# art_limb.net
KiCad netlist of a schematic drawn in EAGLE
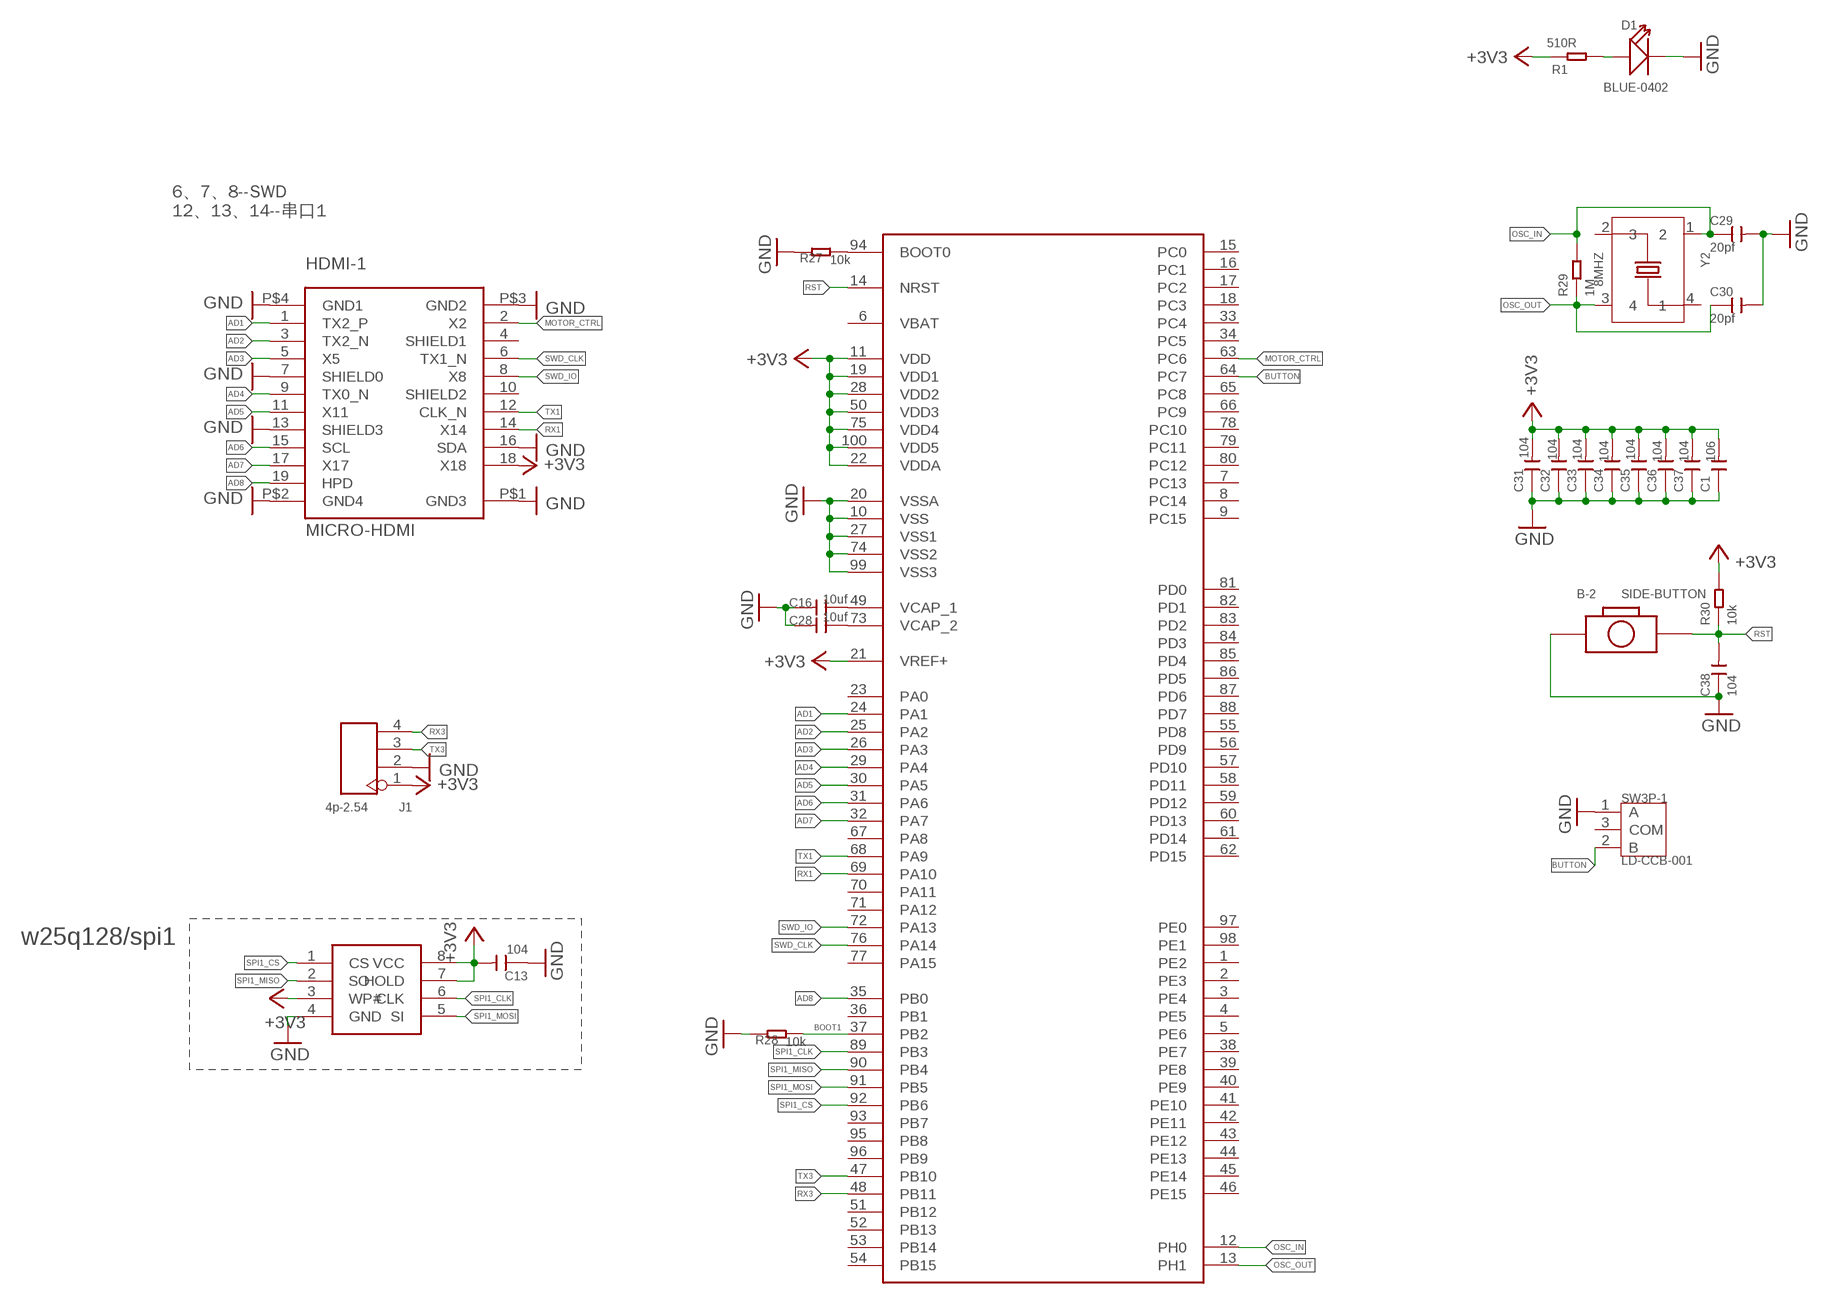
[diagram p0: schematic, sheet 1]

(export (version "E")
  (design (tool "Eeschema 10.0.6"))
  (components
    (comp (ref "B-2")
      (value "SIDE-BUTTON")
      (footprint "eagle-import:SIDE-BUTTON")
      (libsource (lib "eagle-import") (part "SIDE-BUTTON"))
    )
    (comp (ref "C1")
      (value "106")
      (footprint "eagle-import:C0402")
      (fields (field (name "MPN") "GRM1555C1H150JA01D"))
      (libsource (lib "eagle-import") (part "CAP-(0402)"))
    )
    (comp (ref "C13")
      (value "104")
      (footprint "eagle-import:C0402")
      (fields (field (name "MPN") "GRM1555C1H150JA01D"))
      (libsource (lib "eagle-import") (part "CAP-(0402)"))
    )
    (comp (ref "C16")
      (value "10uf")
      (footprint "eagle-import:C0402")
      (fields (field (name "MPN") "GRM1555C1H150JA01D"))
      (libsource (lib "eagle-import") (part "CAP-(0402)"))
    )
    (comp (ref "C28")
      (value "10uf")
      (footprint "eagle-import:C0402")
      (fields (field (name "MPN") "GRM1555C1H150JA01D"))
      (libsource (lib "eagle-import") (part "CAP-(0402)"))
    )
    (comp (ref "C29")
      (value "20pf")
      (footprint "eagle-import:C0402")
      (fields (field (name "MPN") "GRM1555C1H150JA01D"))
      (libsource (lib "eagle-import") (part "CAP-(0402)"))
    )
    (comp (ref "C30")
      (value "20pf")
      (footprint "eagle-import:C0402")
      (fields (field (name "MPN") "GRM1555C1H150JA01D"))
      (libsource (lib "eagle-import") (part "CAP-(0402)"))
    )
    (comp (ref "C31")
      (value "104")
      (footprint "eagle-import:C0402")
      (fields (field (name "MPN") "GRM1555C1H150JA01D"))
      (libsource (lib "eagle-import") (part "CAP-(0402)"))
    )
    (comp (ref "C32")
      (value "104")
      (footprint "eagle-import:C0402")
      (fields (field (name "MPN") "GRM1555C1H150JA01D"))
      (libsource (lib "eagle-import") (part "CAP-(0402)"))
    )
    (comp (ref "C33")
      (value "104")
      (footprint "eagle-import:C0402")
      (fields (field (name "MPN") "GRM1555C1H150JA01D"))
      (libsource (lib "eagle-import") (part "CAP-(0402)"))
    )
    (comp (ref "C34")
      (value "104")
      (footprint "eagle-import:C0402")
      (fields (field (name "MPN") "GRM1555C1H150JA01D"))
      (libsource (lib "eagle-import") (part "CAP-(0402)"))
    )
    (comp (ref "C35")
      (value "104")
      (footprint "eagle-import:C0402")
      (fields (field (name "MPN") "GRM1555C1H150JA01D"))
      (libsource (lib "eagle-import") (part "CAP-(0402)"))
    )
    (comp (ref "C36")
      (value "104")
      (footprint "eagle-import:C0402")
      (fields (field (name "MPN") "GRM1555C1H150JA01D"))
      (libsource (lib "eagle-import") (part "CAP-(0402)"))
    )
    (comp (ref "C37")
      (value "104")
      (footprint "eagle-import:C0402")
      (fields (field (name "MPN") "GRM1555C1H150JA01D"))
      (libsource (lib "eagle-import") (part "CAP-(0402)"))
    )
    (comp (ref "C38")
      (value "104")
      (footprint "eagle-import:C0402")
      (fields (field (name "MPN") "GRM1555C1H150JA01D"))
      (libsource (lib "eagle-import") (part "CAP-(0402)"))
    )
    (comp (ref "D1")
      (value "BLUE-0402")
      (footprint "eagle-import:LED-0402")
      (fields (field (name "MPN") "BL-HB337A-AV-TRB"))
      (libsource (lib "eagle-import") (part "LED-(0402)"))
    )
    (comp (ref "HDMI-1")
      (value "MICRO-HDMI")
      (footprint "eagle-import:HDMI")
      (libsource (lib "eagle-import") (part "MICRO-HDMI"))
    )
    (comp (ref "J1")
      (value "4p-2.54")
      (footprint "eagle-import:H4-2.54")
      (fields (field (name "MPN") "F185-1104A1BSYA1"))
      (libsource (lib "eagle-import") (part "DIP-BLACK-FEMALE-HEADER-VERT(4P-2.54)"))
    )
    (comp (ref "R1")
      (value "510R")
      (footprint "eagle-import:R0402")
      (fields (field (name "MPN") "RC0402JR-070RL"))
      (libsource (lib "eagle-import") (part "RES-(0402)"))
    )
    (comp (ref "R27")
      (value "10k")
      (footprint "eagle-import:R0402")
      (fields (field (name "MPN") "RC0402JR-070RL"))
      (libsource (lib "eagle-import") (part "RES-(0402)"))
    )
    (comp (ref "R28")
      (value "10k")
      (footprint "eagle-import:R0402")
      (fields (field (name "MPN") "RC0402JR-070RL"))
      (libsource (lib "eagle-import") (part "RES-(0402)"))
    )
    (comp (ref "R29")
      (value "1M")
      (footprint "eagle-import:R0402")
      (fields (field (name "MPN") "RC0402JR-070RL"))
      (libsource (lib "eagle-import") (part "RES-(0402)"))
    )
    (comp (ref "R30")
      (value "10k")
      (footprint "eagle-import:R0402")
      (fields (field (name "MPN") "RC0402JR-070RL"))
      (libsource (lib "eagle-import") (part "RES-(0402)"))
    )
    (comp (ref "SW3P-1")
      (value "LD-CCB-001")
      (footprint "eagle-import:SW3-2.54-9.0X3.5X3.5+2.0MM")
      (libsource (lib "eagle-import") (part "SWITCH(3P)"))
    )
    (comp (ref "U$1")
      (value "STM32F40XSTM32D40X")
      (footprint "eagle-import:LQFP100")
      (libsource (lib "eagle-import") (part "STM32F40XSTM32D40X"))
    )
    (comp (ref "W25Q128")
      (value "W25Q128")
      (footprint "eagle-import:SOP08")
      (libsource (lib "eagle-import") (part "W25Q128"))
    )
    (comp (ref "Y2")
      (value "8MHZ")
      (footprint "eagle-import:X4-SMD-3.2X2.5X0.7MM")
      (fields (field (name "MPN") "7M-27.120MAAJ-T"))
      (libsource (lib "eagle-import") (part "SMD-CRYSTAL-27.12MHZ-18PF-30PPM-60R(4P-3.2X2.5MM)"))
    )
  )
  (nets
    (net (code "1") (name "+3V3") (class "Default")
      (node (ref "C1") (pin "2") (pinfunction "2_2") (pintype "passive"))
      (node (ref "C13") (pin "2") (pinfunction "2_2") (pintype "passive"))
      (node (ref "C31") (pin "2") (pinfunction "2_2") (pintype "passive"))
      (node (ref "C32") (pin "2") (pinfunction "2_2") (pintype "passive"))
      (node (ref "C33") (pin "2") (pinfunction "2_2") (pintype "passive"))
      (node (ref "C34") (pin "2") (pinfunction "2_2") (pintype "passive"))
      (node (ref "C35") (pin "2") (pinfunction "2_2") (pintype "passive"))
      (node (ref "C36") (pin "2") (pinfunction "2_2") (pintype "passive"))
      (node (ref "C37") (pin "2") (pinfunction "2_2") (pintype "passive"))
      (node (ref "HDMI-1") (pin "18") (pinfunction "X18_18") (pintype "bidirectional"))
      (node (ref "J1") (pin "1") (pinfunction "P$1_1") (pintype "bidirectional"))
      (node (ref "R1") (pin "2") (pinfunction "2_2") (pintype "passive"))
      (node (ref "R30") (pin "2") (pinfunction "2_2") (pintype "passive"))
      (node (ref "U$1") (pin "100") (pinfunction "VDD5_100") (pintype "bidirectional"))
      (node (ref "U$1") (pin "11") (pinfunction "VDD_11") (pintype "bidirectional"))
      (node (ref "U$1") (pin "19") (pinfunction "VDD1_19") (pintype "bidirectional"))
      (node (ref "U$1") (pin "21") (pinfunction "VREF+_21") (pintype "bidirectional"))
      (node (ref "U$1") (pin "22") (pinfunction "VDDA_22") (pintype "bidirectional"))
      (node (ref "U$1") (pin "28") (pinfunction "VDD2_28") (pintype "bidirectional"))
      (node (ref "U$1") (pin "50") (pinfunction "VDD3_50") (pintype "bidirectional"))
      (node (ref "U$1") (pin "75") (pinfunction "VDD4_75") (pintype "bidirectional"))
      (node (ref "W25Q128") (pin "3") (pinfunction "WP#_3") (pintype "bidirectional"))
      (node (ref "W25Q128") (pin "7") (pinfunction "HOLD_7") (pintype "bidirectional"))
      (node (ref "W25Q128") (pin "8") (pinfunction "VCC_8") (pintype "bidirectional"))
    )
    (net (code "2") (name "/BOOT1") (class "Default")
      (node (ref "R28") (pin "2") (pinfunction "2_2") (pintype "passive"))
      (node (ref "U$1") (pin "37") (pinfunction "PB2_37") (pintype "bidirectional"))
    )
    (net (code "3") (name "AD1") (class "Default")
      (node (ref "HDMI-1") (pin "1") (pinfunction "TX2_P_1") (pintype "bidirectional"))
      (node (ref "U$1") (pin "24") (pinfunction "PA1_24") (pintype "bidirectional"))
    )
    (net (code "4") (name "AD2") (class "Default")
      (node (ref "HDMI-1") (pin "3") (pinfunction "TX2_N_3") (pintype "bidirectional"))
      (node (ref "U$1") (pin "25") (pinfunction "PA2_25") (pintype "bidirectional"))
    )
    (net (code "5") (name "AD3") (class "Default")
      (node (ref "HDMI-1") (pin "5") (pinfunction "X5_5") (pintype "bidirectional"))
      (node (ref "U$1") (pin "26") (pinfunction "PA3_26") (pintype "bidirectional"))
    )
    (net (code "6") (name "AD4") (class "Default")
      (node (ref "HDMI-1") (pin "9") (pinfunction "TX0_N_9") (pintype "bidirectional"))
      (node (ref "U$1") (pin "29") (pinfunction "PA4_29") (pintype "bidirectional"))
    )
    (net (code "7") (name "AD5") (class "Default")
      (node (ref "HDMI-1") (pin "11") (pinfunction "X11_11") (pintype "bidirectional"))
      (node (ref "U$1") (pin "30") (pinfunction "PA5_30") (pintype "bidirectional"))
    )
    (net (code "8") (name "AD6") (class "Default")
      (node (ref "HDMI-1") (pin "15") (pinfunction "SCL_15") (pintype "bidirectional"))
      (node (ref "U$1") (pin "31") (pinfunction "PA6_31") (pintype "bidirectional"))
    )
    (net (code "9") (name "AD7") (class "Default")
      (node (ref "HDMI-1") (pin "17") (pinfunction "X17_17") (pintype "bidirectional"))
      (node (ref "U$1") (pin "32") (pinfunction "PA7_32") (pintype "bidirectional"))
    )
    (net (code "10") (name "AD8") (class "Default")
      (node (ref "HDMI-1") (pin "19") (pinfunction "HPD_19") (pintype "bidirectional"))
      (node (ref "U$1") (pin "35") (pinfunction "PB0_35") (pintype "bidirectional"))
    )
    (net (code "11") (name "BUTTON") (class "Default")
      (node (ref "SW3P-1") (pin "2") (pinfunction "B_2") (pintype "bidirectional"))
      (node (ref "U$1") (pin "64") (pinfunction "PC7_64") (pintype "bidirectional"))
    )
    (net (code "12") (name "GND") (class "Default")
      (node (ref "B-2") (pin "P$2") (pinfunction "1_P$2") (pintype "bidirectional"))
      (node (ref "C1") (pin "1") (pinfunction "1_1") (pintype "passive"))
      (node (ref "C13") (pin "1") (pinfunction "1_1") (pintype "passive"))
      (node (ref "C16") (pin "2") (pinfunction "2_2") (pintype "passive"))
      (node (ref "C28") (pin "2") (pinfunction "2_2") (pintype "passive"))
      (node (ref "C29") (pin "2") (pinfunction "2_2") (pintype "passive"))
      (node (ref "C30") (pin "2") (pinfunction "2_2") (pintype "passive"))
      (node (ref "C31") (pin "1") (pinfunction "1_1") (pintype "passive"))
      (node (ref "C32") (pin "1") (pinfunction "1_1") (pintype "passive"))
      (node (ref "C33") (pin "1") (pinfunction "1_1") (pintype "passive"))
      (node (ref "C34") (pin "1") (pinfunction "1_1") (pintype "passive"))
      (node (ref "C35") (pin "1") (pinfunction "1_1") (pintype "passive"))
      (node (ref "C36") (pin "1") (pinfunction "1_1") (pintype "passive"))
      (node (ref "C37") (pin "1") (pinfunction "1_1") (pintype "passive"))
      (node (ref "C38") (pin "1") (pinfunction "1_1") (pintype "passive"))
      (node (ref "D1") (pin "-") (pinfunction "-_-") (pintype "passive"))
      (node (ref "HDMI-1") (pin "13") (pinfunction "SHIELD3_13") (pintype "bidirectional"))
      (node (ref "HDMI-1") (pin "16") (pinfunction "SDA_16") (pintype "bidirectional"))
      (node (ref "HDMI-1") (pin "7") (pinfunction "SHIELD0_7") (pintype "bidirectional"))
      (node (ref "HDMI-1") (pin "P$1") (pinfunction "GND3_P$1") (pintype "bidirectional"))
      (node (ref "HDMI-1") (pin "P$2") (pinfunction "GND4_P$2") (pintype "bidirectional"))
      (node (ref "HDMI-1") (pin "P$3") (pinfunction "GND2_P$3") (pintype "bidirectional"))
      (node (ref "HDMI-1") (pin "P$4") (pinfunction "GND1_P$4") (pintype "bidirectional"))
      (node (ref "J1") (pin "2") (pinfunction "P$2_2") (pintype "bidirectional"))
      (node (ref "R27") (pin "1") (pinfunction "1_1") (pintype "passive"))
      (node (ref "R28") (pin "1") (pinfunction "1_1") (pintype "passive"))
      (node (ref "SW3P-1") (pin "1") (pinfunction "A_1") (pintype "bidirectional"))
      (node (ref "U$1") (pin "10") (pinfunction "VSS_10") (pintype "bidirectional"))
      (node (ref "U$1") (pin "20") (pinfunction "VSSA_20") (pintype "bidirectional"))
      (node (ref "U$1") (pin "27") (pinfunction "VSS1_27") (pintype "bidirectional"))
      (node (ref "U$1") (pin "74") (pinfunction "VSS2_74") (pintype "bidirectional"))
      (node (ref "U$1") (pin "99") (pinfunction "VSS3_99") (pintype "bidirectional"))
      (node (ref "W25Q128") (pin "4") (pinfunction "GND_4") (pintype "bidirectional"))
    )
    (net (code "13") (name "MOTOR_CTRL") (class "Default")
      (node (ref "HDMI-1") (pin "2") (pinfunction "X2_2") (pintype "bidirectional"))
      (node (ref "U$1") (pin "63") (pinfunction "PC6_63") (pintype "bidirectional"))
    )
    (net (code "14") (name "Net-(D1-Pad+)") (class "Default")
      (node (ref "D1") (pin "+") (pinfunction "+_+") (pintype "passive"))
      (node (ref "R1") (pin "1") (pinfunction "1_1") (pintype "passive"))
    )
    (net (code "15") (name "Net-(U$1-BOOT0)") (class "Default")
      (node (ref "R27") (pin "2") (pinfunction "2_2") (pintype "passive"))
      (node (ref "U$1") (pin "94") (pinfunction "BOOT0_94") (pintype "bidirectional"))
    )
    (net (code "16") (name "Net-(U$1-VCAP_1)") (class "Default")
      (node (ref "C16") (pin "1") (pinfunction "1_1") (pintype "passive"))
      (node (ref "U$1") (pin "49") (pinfunction "VCAP_1_49") (pintype "bidirectional"))
    )
    (net (code "17") (name "Net-(U$1-VCAP_2)") (class "Default")
      (node (ref "C28") (pin "1") (pinfunction "1_1") (pintype "passive"))
      (node (ref "U$1") (pin "73") (pinfunction "VCAP_2_73") (pintype "bidirectional"))
    )
    (net (code "18") (name "OSC_IN") (class "Default")
      (node (ref "C29") (pin "1") (pinfunction "1_1") (pintype "passive"))
      (node (ref "R29") (pin "2") (pinfunction "2_2") (pintype "passive"))
      (node (ref "U$1") (pin "12") (pinfunction "PH0_12") (pintype "bidirectional"))
      (node (ref "Y2") (pin "1") (pinfunction "2_1") (pintype "bidirectional"))
    )
    (net (code "19") (name "OSC_OUT") (class "Default")
      (node (ref "C30") (pin "1") (pinfunction "1_1") (pintype "passive"))
      (node (ref "R29") (pin "1") (pinfunction "1_1") (pintype "passive"))
      (node (ref "U$1") (pin "13") (pinfunction "PH1_13") (pintype "bidirectional"))
      (node (ref "Y2") (pin "3") (pinfunction "4_3") (pintype "bidirectional"))
    )
    (net (code "20") (name "RST") (class "Default")
      (node (ref "B-2") (pin "P$1") (pinfunction "2_P$1") (pintype "bidirectional"))
      (node (ref "C38") (pin "2") (pinfunction "2_2") (pintype "passive"))
      (node (ref "R30") (pin "1") (pinfunction "1_1") (pintype "passive"))
      (node (ref "U$1") (pin "14") (pinfunction "NRST_14") (pintype "bidirectional"))
    )
    (net (code "21") (name "RX1") (class "Default")
      (node (ref "HDMI-1") (pin "14") (pinfunction "X14_14") (pintype "bidirectional"))
      (node (ref "U$1") (pin "69") (pinfunction "PA10_69") (pintype "bidirectional"))
    )
    (net (code "22") (name "RX3") (class "Default")
      (node (ref "J1") (pin "4") (pinfunction "P$4_4") (pintype "bidirectional"))
      (node (ref "U$1") (pin "48") (pinfunction "PB11_48") (pintype "bidirectional"))
    )
    (net (code "23") (name "SPI1_CLK") (class "Default")
      (node (ref "U$1") (pin "89") (pinfunction "PB3_89") (pintype "bidirectional"))
      (node (ref "W25Q128") (pin "6") (pinfunction "CLK_6") (pintype "bidirectional"))
    )
    (net (code "24") (name "SPI1_CS") (class "Default")
      (node (ref "U$1") (pin "92") (pinfunction "PB6_92") (pintype "bidirectional"))
      (node (ref "W25Q128") (pin "1") (pinfunction "CS_1") (pintype "bidirectional"))
    )
    (net (code "25") (name "SPI1_MISO") (class "Default")
      (node (ref "U$1") (pin "90") (pinfunction "PB4_90") (pintype "bidirectional"))
      (node (ref "W25Q128") (pin "2") (pinfunction "SO_2") (pintype "bidirectional"))
    )
    (net (code "26") (name "SPI1_MOSI") (class "Default")
      (node (ref "U$1") (pin "91") (pinfunction "PB5_91") (pintype "bidirectional"))
      (node (ref "W25Q128") (pin "5") (pinfunction "SI_5") (pintype "bidirectional"))
    )
    (net (code "27") (name "SWD_CLK") (class "Default")
      (node (ref "HDMI-1") (pin "6") (pinfunction "TX1_N_6") (pintype "bidirectional"))
      (node (ref "U$1") (pin "76") (pinfunction "PA14_76") (pintype "bidirectional"))
    )
    (net (code "28") (name "SWD_IO") (class "Default")
      (node (ref "HDMI-1") (pin "8") (pinfunction "X8_8") (pintype "bidirectional"))
      (node (ref "U$1") (pin "72") (pinfunction "PA13_72") (pintype "bidirectional"))
    )
    (net (code "29") (name "TX1") (class "Default")
      (node (ref "HDMI-1") (pin "12") (pinfunction "CLK_N_12") (pintype "bidirectional"))
      (node (ref "U$1") (pin "68") (pinfunction "PA9_68") (pintype "bidirectional"))
    )
    (net (code "30") (name "TX3") (class "Default")
      (node (ref "J1") (pin "3") (pinfunction "P$3_3") (pintype "bidirectional"))
      (node (ref "U$1") (pin "47") (pinfunction "PB10_47") (pintype "bidirectional"))
    )
    (net (code "31") (name "unconnected-(HDMI-1-SHIELD1-Pad4)") (class "Default")
      (node (ref "HDMI-1") (pin "4") (pinfunction "SHIELD1_4") (pintype "bidirectional"))
    )
    (net (code "32") (name "unconnected-(HDMI-1-SHIELD2-Pad10)") (class "Default")
      (node (ref "HDMI-1") (pin "10") (pinfunction "SHIELD2_10") (pintype "bidirectional"))
    )
    (net (code "33") (name "unconnected-(SW3P-1-COM-Pad3)") (class "Default")
      (node (ref "SW3P-1") (pin "3") (pinfunction "COM_3") (pintype "bidirectional"))
    )
    (net (code "34") (name "unconnected-(U$1-PA0-Pad23)") (class "Default")
      (node (ref "U$1") (pin "23") (pinfunction "PA0_23") (pintype "bidirectional"))
    )
    (net (code "35") (name "unconnected-(U$1-PA8-Pad67)") (class "Default")
      (node (ref "U$1") (pin "67") (pinfunction "PA8_67") (pintype "bidirectional"))
    )
    (net (code "36") (name "unconnected-(U$1-PA11-Pad70)") (class "Default")
      (node (ref "U$1") (pin "70") (pinfunction "PA11_70") (pintype "bidirectional"))
    )
    (net (code "37") (name "unconnected-(U$1-PA12-Pad71)") (class "Default")
      (node (ref "U$1") (pin "71") (pinfunction "PA12_71") (pintype "bidirectional"))
    )
    (net (code "38") (name "unconnected-(U$1-PA15-Pad77)") (class "Default")
      (node (ref "U$1") (pin "77") (pinfunction "PA15_77") (pintype "bidirectional"))
    )
    (net (code "39") (name "unconnected-(U$1-PB1-Pad36)") (class "Default")
      (node (ref "U$1") (pin "36") (pinfunction "PB1_36") (pintype "bidirectional"))
    )
    (net (code "40") (name "unconnected-(U$1-PB7-Pad93)") (class "Default")
      (node (ref "U$1") (pin "93") (pinfunction "PB7_93") (pintype "bidirectional"))
    )
    (net (code "41") (name "unconnected-(U$1-PB8-Pad95)") (class "Default")
      (node (ref "U$1") (pin "95") (pinfunction "PB8_95") (pintype "bidirectional"))
    )
    (net (code "42") (name "unconnected-(U$1-PB9-Pad96)") (class "Default")
      (node (ref "U$1") (pin "96") (pinfunction "PB9_96") (pintype "bidirectional"))
    )
    (net (code "43") (name "unconnected-(U$1-PB12-Pad51)") (class "Default")
      (node (ref "U$1") (pin "51") (pinfunction "PB12_51") (pintype "bidirectional"))
    )
    (net (code "44") (name "unconnected-(U$1-PB13-Pad52)") (class "Default")
      (node (ref "U$1") (pin "52") (pinfunction "PB13_52") (pintype "bidirectional"))
    )
    (net (code "45") (name "unconnected-(U$1-PB14-Pad53)") (class "Default")
      (node (ref "U$1") (pin "53") (pinfunction "PB14_53") (pintype "bidirectional"))
    )
    (net (code "46") (name "unconnected-(U$1-PB15-Pad54)") (class "Default")
      (node (ref "U$1") (pin "54") (pinfunction "PB15_54") (pintype "bidirectional"))
    )
    (net (code "47") (name "unconnected-(U$1-PC0-Pad15)") (class "Default")
      (node (ref "U$1") (pin "15") (pinfunction "PC0_15") (pintype "bidirectional"))
    )
    (net (code "48") (name "unconnected-(U$1-PC1-Pad16)") (class "Default")
      (node (ref "U$1") (pin "16") (pinfunction "PC1_16") (pintype "bidirectional"))
    )
    (net (code "49") (name "unconnected-(U$1-PC2-Pad17)") (class "Default")
      (node (ref "U$1") (pin "17") (pinfunction "PC2_17") (pintype "bidirectional"))
    )
    (net (code "50") (name "unconnected-(U$1-PC3-Pad18)") (class "Default")
      (node (ref "U$1") (pin "18") (pinfunction "PC3_18") (pintype "bidirectional"))
    )
    (net (code "51") (name "unconnected-(U$1-PC4-Pad33)") (class "Default")
      (node (ref "U$1") (pin "33") (pinfunction "PC4_33") (pintype "bidirectional"))
    )
    (net (code "52") (name "unconnected-(U$1-PC5-Pad34)") (class "Default")
      (node (ref "U$1") (pin "34") (pinfunction "PC5_34") (pintype "bidirectional"))
    )
    (net (code "53") (name "unconnected-(U$1-PC8-Pad65)") (class "Default")
      (node (ref "U$1") (pin "65") (pinfunction "PC8_65") (pintype "bidirectional"))
    )
    (net (code "54") (name "unconnected-(U$1-PC9-Pad66)") (class "Default")
      (node (ref "U$1") (pin "66") (pinfunction "PC9_66") (pintype "bidirectional"))
    )
    (net (code "55") (name "unconnected-(U$1-PC10-Pad78)") (class "Default")
      (node (ref "U$1") (pin "78") (pinfunction "PC10_78") (pintype "bidirectional"))
    )
    (net (code "56") (name "unconnected-(U$1-PC11-Pad79)") (class "Default")
      (node (ref "U$1") (pin "79") (pinfunction "PC11_79") (pintype "bidirectional"))
    )
    (net (code "57") (name "unconnected-(U$1-PC12-Pad80)") (class "Default")
      (node (ref "U$1") (pin "80") (pinfunction "PC12_80") (pintype "bidirectional"))
    )
    (net (code "58") (name "unconnected-(U$1-PC13-Pad7)") (class "Default")
      (node (ref "U$1") (pin "7") (pinfunction "PC13_7") (pintype "bidirectional"))
    )
    (net (code "59") (name "unconnected-(U$1-PC14-Pad8)") (class "Default")
      (node (ref "U$1") (pin "8") (pinfunction "PC14_8") (pintype "bidirectional"))
    )
    (net (code "60") (name "unconnected-(U$1-PC15-Pad9)") (class "Default")
      (node (ref "U$1") (pin "9") (pinfunction "PC15_9") (pintype "bidirectional"))
    )
    (net (code "61") (name "unconnected-(U$1-PD0-Pad81)") (class "Default")
      (node (ref "U$1") (pin "81") (pinfunction "PD0_81") (pintype "bidirectional"))
    )
    (net (code "62") (name "unconnected-(U$1-PD1-Pad82)") (class "Default")
      (node (ref "U$1") (pin "82") (pinfunction "PD1_82") (pintype "bidirectional"))
    )
    (net (code "63") (name "unconnected-(U$1-PD2-Pad83)") (class "Default")
      (node (ref "U$1") (pin "83") (pinfunction "PD2_83") (pintype "bidirectional"))
    )
    (net (code "64") (name "unconnected-(U$1-PD3-Pad84)") (class "Default")
      (node (ref "U$1") (pin "84") (pinfunction "PD3_84") (pintype "bidirectional"))
    )
    (net (code "65") (name "unconnected-(U$1-PD4-Pad85)") (class "Default")
      (node (ref "U$1") (pin "85") (pinfunction "PD4_85") (pintype "bidirectional"))
    )
    (net (code "66") (name "unconnected-(U$1-PD5-Pad86)") (class "Default")
      (node (ref "U$1") (pin "86") (pinfunction "PD5_86") (pintype "bidirectional"))
    )
    (net (code "67") (name "unconnected-(U$1-PD6-Pad87)") (class "Default")
      (node (ref "U$1") (pin "87") (pinfunction "PD6_87") (pintype "bidirectional"))
    )
    (net (code "68") (name "unconnected-(U$1-PD7-Pad88)") (class "Default")
      (node (ref "U$1") (pin "88") (pinfunction "PD7_88") (pintype "bidirectional"))
    )
    (net (code "69") (name "unconnected-(U$1-PD8-Pad55)") (class "Default")
      (node (ref "U$1") (pin "55") (pinfunction "PD8_55") (pintype "bidirectional"))
    )
    (net (code "70") (name "unconnected-(U$1-PD9-Pad56)") (class "Default")
      (node (ref "U$1") (pin "56") (pinfunction "PD9_56") (pintype "bidirectional"))
    )
    (net (code "71") (name "unconnected-(U$1-PD10-Pad57)") (class "Default")
      (node (ref "U$1") (pin "57") (pinfunction "PD10_57") (pintype "bidirectional"))
    )
    (net (code "72") (name "unconnected-(U$1-PD11-Pad58)") (class "Default")
      (node (ref "U$1") (pin "58") (pinfunction "PD11_58") (pintype "bidirectional"))
    )
    (net (code "73") (name "unconnected-(U$1-PD12-Pad59)") (class "Default")
      (node (ref "U$1") (pin "59") (pinfunction "PD12_59") (pintype "bidirectional"))
    )
    (net (code "74") (name "unconnected-(U$1-PD13-Pad60)") (class "Default")
      (node (ref "U$1") (pin "60") (pinfunction "PD13_60") (pintype "bidirectional"))
    )
    (net (code "75") (name "unconnected-(U$1-PD14-Pad61)") (class "Default")
      (node (ref "U$1") (pin "61") (pinfunction "PD14_61") (pintype "bidirectional"))
    )
    (net (code "76") (name "unconnected-(U$1-PD15-Pad62)") (class "Default")
      (node (ref "U$1") (pin "62") (pinfunction "PD15_62") (pintype "bidirectional"))
    )
    (net (code "77") (name "unconnected-(U$1-PE0-Pad97)") (class "Default")
      (node (ref "U$1") (pin "97") (pinfunction "PE0_97") (pintype "bidirectional"))
    )
    (net (code "78") (name "unconnected-(U$1-PE1-Pad98)") (class "Default")
      (node (ref "U$1") (pin "98") (pinfunction "PE1_98") (pintype "bidirectional"))
    )
    (net (code "79") (name "unconnected-(U$1-PE2-Pad1)") (class "Default")
      (node (ref "U$1") (pin "1") (pinfunction "PE2_1") (pintype "bidirectional"))
    )
    (net (code "80") (name "unconnected-(U$1-PE3-Pad2)") (class "Default")
      (node (ref "U$1") (pin "2") (pinfunction "PE3_2") (pintype "bidirectional"))
    )
    (net (code "81") (name "unconnected-(U$1-PE4-Pad3)") (class "Default")
      (node (ref "U$1") (pin "3") (pinfunction "PE4_3") (pintype "bidirectional"))
    )
    (net (code "82") (name "unconnected-(U$1-PE5-Pad4)") (class "Default")
      (node (ref "U$1") (pin "4") (pinfunction "PE5_4") (pintype "bidirectional"))
    )
    (net (code "83") (name "unconnected-(U$1-PE6-Pad5)") (class "Default")
      (node (ref "U$1") (pin "5") (pinfunction "PE6_5") (pintype "bidirectional"))
    )
    (net (code "84") (name "unconnected-(U$1-PE7-Pad38)") (class "Default")
      (node (ref "U$1") (pin "38") (pinfunction "PE7_38") (pintype "bidirectional"))
    )
    (net (code "85") (name "unconnected-(U$1-PE8-Pad39)") (class "Default")
      (node (ref "U$1") (pin "39") (pinfunction "PE8_39") (pintype "bidirectional"))
    )
    (net (code "86") (name "unconnected-(U$1-PE9-Pad40)") (class "Default")
      (node (ref "U$1") (pin "40") (pinfunction "PE9_40") (pintype "bidirectional"))
    )
    (net (code "87") (name "unconnected-(U$1-PE10-Pad41)") (class "Default")
      (node (ref "U$1") (pin "41") (pinfunction "PE10_41") (pintype "bidirectional"))
    )
    (net (code "88") (name "unconnected-(U$1-PE11-Pad42)") (class "Default")
      (node (ref "U$1") (pin "42") (pinfunction "PE11_42") (pintype "bidirectional"))
    )
    (net (code "89") (name "unconnected-(U$1-PE12-Pad43)") (class "Default")
      (node (ref "U$1") (pin "43") (pinfunction "PE12_43") (pintype "bidirectional"))
    )
    (net (code "90") (name "unconnected-(U$1-PE13-Pad44)") (class "Default")
      (node (ref "U$1") (pin "44") (pinfunction "PE13_44") (pintype "bidirectional"))
    )
    (net (code "91") (name "unconnected-(U$1-PE14-Pad45)") (class "Default")
      (node (ref "U$1") (pin "45") (pinfunction "PE14_45") (pintype "bidirectional"))
    )
    (net (code "92") (name "unconnected-(U$1-PE15-Pad46)") (class "Default")
      (node (ref "U$1") (pin "46") (pinfunction "PE15_46") (pintype "bidirectional"))
    )
    (net (code "93") (name "unconnected-(U$1-VBAT-Pad6)") (class "Default")
      (node (ref "U$1") (pin "6") (pinfunction "VBAT_6") (pintype "bidirectional"))
    )
    (net (code "94") (name "unconnected-(Y2-1-Pad4)") (class "Default")
      (node (ref "Y2") (pin "4") (pinfunction "1_4") (pintype "bidirectional"))
    )
    (net (code "95") (name "unconnected-(Y2-3-Pad2)") (class "Default")
      (node (ref "Y2") (pin "2") (pinfunction "3_2") (pintype "bidirectional"))
    )
  )
)
